# Sheet1.net
KiCad netlist of a schematic drawn in Altium Designer
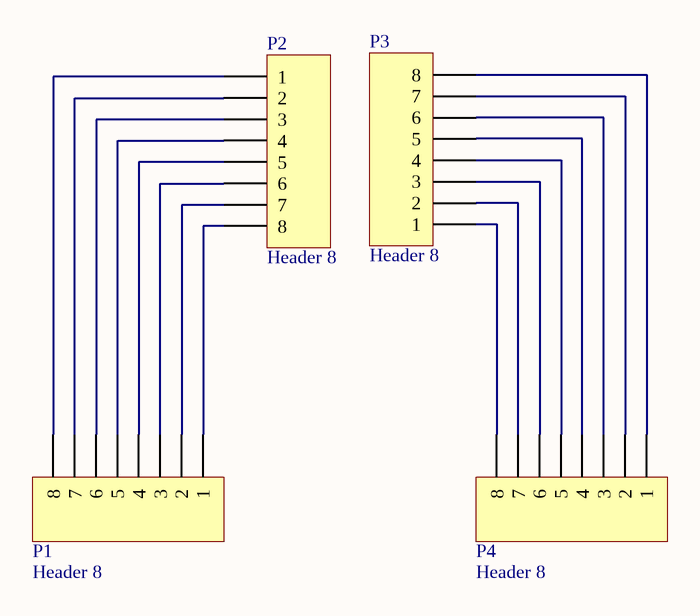
[diagram p0: Sheet1.SchDoc]

(export (version "E")
  (design (tool "Eeschema 10.0.6"))
  (components
    (comp (ref "P1")
      (value "Header 8")
      (footprint "HDR1X8")
      (description "Header, 8-Pin")
      (fields (field (name "PUBLISHER") "Altium Limited"))
      (libsource (lib "Miscellaneous Connectors") (part "Header 8"))
    )
    (comp (ref "P2")
      (value "Header 8")
      (footprint "HDR1X8")
      (description "Header, 8-Pin")
      (fields (field (name "PUBLISHER") "Altium Limited"))
      (libsource (lib "") (part "Header 8_2"))
    )
    (comp (ref "P3")
      (value "Header 8")
      (footprint "HDR1X8")
      (description "Header, 8-Pin")
      (fields (field (name "PUBLISHER") "Altium Limited"))
      (libsource (lib "") (part "Header 8_1"))
    )
    (comp (ref "P4")
      (value "Header 8")
      (footprint "HDR1X8")
      (description "Header, 8-Pin")
      (fields (field (name "PUBLISHER") "Altium Limited"))
      (libsource (lib "Miscellaneous Connectors") (part "Header 8"))
    )
  )
  (nets
    (net (code "1") (name "Net-(P1-Pad1)") (class "Default")
      (node (ref "P1") (pin "1") (pinfunction "1_1") (pintype "passive"))
      (node (ref "P2") (pin "8") (pinfunction "8_8") (pintype "passive"))
    )
    (net (code "2") (name "Net-(P1-Pad2)") (class "Default")
      (node (ref "P1") (pin "2") (pinfunction "2_2") (pintype "passive"))
      (node (ref "P2") (pin "7") (pinfunction "7_7") (pintype "passive"))
    )
    (net (code "3") (name "Net-(P1-Pad3)") (class "Default")
      (node (ref "P1") (pin "3") (pinfunction "3_3") (pintype "passive"))
      (node (ref "P2") (pin "6") (pinfunction "6_6") (pintype "passive"))
    )
    (net (code "4") (name "Net-(P1-Pad4)") (class "Default")
      (node (ref "P1") (pin "4") (pinfunction "4_4") (pintype "passive"))
      (node (ref "P2") (pin "5") (pinfunction "5_5") (pintype "passive"))
    )
    (net (code "5") (name "Net-(P1-Pad5)") (class "Default")
      (node (ref "P1") (pin "5") (pinfunction "5_5") (pintype "passive"))
      (node (ref "P2") (pin "4") (pinfunction "4_4") (pintype "passive"))
    )
    (net (code "6") (name "Net-(P1-Pad6)") (class "Default")
      (node (ref "P1") (pin "6") (pinfunction "6_6") (pintype "passive"))
      (node (ref "P2") (pin "3") (pinfunction "3_3") (pintype "passive"))
    )
    (net (code "7") (name "Net-(P1-Pad7)") (class "Default")
      (node (ref "P1") (pin "7") (pinfunction "7_7") (pintype "passive"))
      (node (ref "P2") (pin "2") (pinfunction "2_2") (pintype "passive"))
    )
    (net (code "8") (name "Net-(P1-Pad8)") (class "Default")
      (node (ref "P1") (pin "8") (pinfunction "8_8") (pintype "passive"))
      (node (ref "P2") (pin "1") (pinfunction "1_1") (pintype "passive"))
    )
    (net (code "9") (name "Net-(P3-Pad1)") (class "Default")
      (node (ref "P3") (pin "1") (pinfunction "1_1") (pintype "passive"))
      (node (ref "P4") (pin "8") (pinfunction "8_8") (pintype "passive"))
    )
    (net (code "10") (name "Net-(P3-Pad2)") (class "Default")
      (node (ref "P3") (pin "2") (pinfunction "2_2") (pintype "passive"))
      (node (ref "P4") (pin "7") (pinfunction "7_7") (pintype "passive"))
    )
    (net (code "11") (name "Net-(P3-Pad3)") (class "Default")
      (node (ref "P3") (pin "3") (pinfunction "3_3") (pintype "passive"))
      (node (ref "P4") (pin "6") (pinfunction "6_6") (pintype "passive"))
    )
    (net (code "12") (name "Net-(P3-Pad4)") (class "Default")
      (node (ref "P3") (pin "4") (pinfunction "4_4") (pintype "passive"))
      (node (ref "P4") (pin "5") (pinfunction "5_5") (pintype "passive"))
    )
    (net (code "13") (name "Net-(P3-Pad5)") (class "Default")
      (node (ref "P3") (pin "5") (pinfunction "5_5") (pintype "passive"))
      (node (ref "P4") (pin "4") (pinfunction "4_4") (pintype "passive"))
    )
    (net (code "14") (name "Net-(P3-Pad6)") (class "Default")
      (node (ref "P3") (pin "6") (pinfunction "6_6") (pintype "passive"))
      (node (ref "P4") (pin "3") (pinfunction "3_3") (pintype "passive"))
    )
    (net (code "15") (name "Net-(P3-Pad7)") (class "Default")
      (node (ref "P3") (pin "7") (pinfunction "7_7") (pintype "passive"))
      (node (ref "P4") (pin "2") (pinfunction "2_2") (pintype "passive"))
    )
    (net (code "16") (name "Net-(P3-Pad8)") (class "Default")
      (node (ref "P3") (pin "8") (pinfunction "8_8") (pintype "passive"))
      (node (ref "P4") (pin "1") (pinfunction "1_1") (pintype "passive"))
    )
  )
)
